# ButtonPad.net
KiCad netlist of a schematic drawn in EAGLE
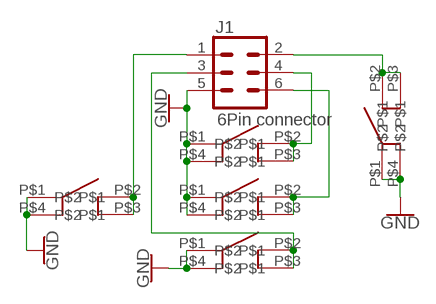
[diagram p0: schematic, sheet 1]

(export (version "E")
  (design (tool "Eeschema 10.0.6"))
  (components
    (comp (ref "J1")
      (value "6Pin connector")
      (footprint "eagle-import:2X3")
      (libsource (lib "eagle-import") (part "CONN_03X22X3_SILK_MALE_PTH"))
    )
    (comp (ref "U$1")
      (value "BUTTON_GRAY_12MM")
      (footprint "eagle-import:BUTTON_12MM")
      (libsource (lib "eagle-import") (part "BUTTON_GRAY_12MM"))
    )
    (comp (ref "U$2")
      (value "BUTTON_GRAY_12MM")
      (footprint "eagle-import:BUTTON_12MM")
      (libsource (lib "eagle-import") (part "BUTTON_GRAY_12MM"))
    )
    (comp (ref "U$3")
      (value "BUTTON_GRAY_12MM")
      (footprint "eagle-import:BUTTON_12MM")
      (libsource (lib "eagle-import") (part "BUTTON_GRAY_12MM"))
    )
    (comp (ref "U$4")
      (value "BUTTON_GRAY_12MM")
      (footprint "eagle-import:BUTTON_12MM")
      (libsource (lib "eagle-import") (part "BUTTON_GRAY_12MM"))
    )
    (comp (ref "U$5")
      (value "BUTTON_GRAY_12MM")
      (footprint "eagle-import:BUTTON_12MM")
      (libsource (lib "eagle-import") (part "BUTTON_GRAY_12MM"))
    )
  )
  (nets
    (net (code "1") (name "GND") (class "Default")
      (node (ref "J1") (pin "5") (pinfunction "5_5") (pintype "bidirectional"))
      (node (ref "U$1") (pin "P$1") (pinfunction "P$1_P$1") (pintype "bidirectional"))
      (node (ref "U$1") (pin "P$4") (pinfunction "P$1_P$4") (pintype "bidirectional"))
      (node (ref "U$2") (pin "P$1") (pinfunction "P$1_P$1") (pintype "bidirectional"))
      (node (ref "U$2") (pin "P$4") (pinfunction "P$1_P$4") (pintype "bidirectional"))
      (node (ref "U$3") (pin "P$1") (pinfunction "P$1_P$1") (pintype "bidirectional"))
      (node (ref "U$3") (pin "P$4") (pinfunction "P$1_P$4") (pintype "bidirectional"))
      (node (ref "U$4") (pin "P$1") (pinfunction "P$1_P$1") (pintype "bidirectional"))
      (node (ref "U$4") (pin "P$4") (pinfunction "P$1_P$4") (pintype "bidirectional"))
      (node (ref "U$5") (pin "P$1") (pinfunction "P$1_P$1") (pintype "bidirectional"))
      (node (ref "U$5") (pin "P$4") (pinfunction "P$1_P$4") (pintype "bidirectional"))
    )
    (net (code "2") (name "Net-(J1-Pad1)") (class "Default")
      (node (ref "J1") (pin "1") (pinfunction "1_1") (pintype "bidirectional"))
      (node (ref "U$5") (pin "P$2") (pinfunction "P$2_P$2") (pintype "bidirectional"))
      (node (ref "U$5") (pin "P$3") (pinfunction "P$2_P$3") (pintype "bidirectional"))
    )
    (net (code "3") (name "Net-(J1-Pad2)") (class "Default")
      (node (ref "J1") (pin "2") (pinfunction "2_2") (pintype "bidirectional"))
      (node (ref "U$4") (pin "P$2") (pinfunction "P$2_P$2") (pintype "bidirectional"))
      (node (ref "U$4") (pin "P$3") (pinfunction "P$2_P$3") (pintype "bidirectional"))
    )
    (net (code "4") (name "Net-(J1-Pad3)") (class "Default")
      (node (ref "J1") (pin "3") (pinfunction "3_3") (pintype "bidirectional"))
      (node (ref "U$3") (pin "P$2") (pinfunction "P$2_P$2") (pintype "bidirectional"))
      (node (ref "U$3") (pin "P$3") (pinfunction "P$2_P$3") (pintype "bidirectional"))
    )
    (net (code "5") (name "Net-(J1-Pad4)") (class "Default")
      (node (ref "J1") (pin "4") (pinfunction "4_4") (pintype "bidirectional"))
      (node (ref "U$1") (pin "P$2") (pinfunction "P$2_P$2") (pintype "bidirectional"))
      (node (ref "U$1") (pin "P$3") (pinfunction "P$2_P$3") (pintype "bidirectional"))
    )
    (net (code "6") (name "Net-(J1-Pad6)") (class "Default")
      (node (ref "J1") (pin "6") (pinfunction "6_6") (pintype "bidirectional"))
      (node (ref "U$2") (pin "P$2") (pinfunction "P$2_P$2") (pintype "bidirectional"))
      (node (ref "U$2") (pin "P$3") (pinfunction "P$2_P$3") (pintype "bidirectional"))
    )
  )
)
